# explorator_mainboard_v1_large_1_1_photo_.net
KiCad netlist of a schematic drawn in EAGLE
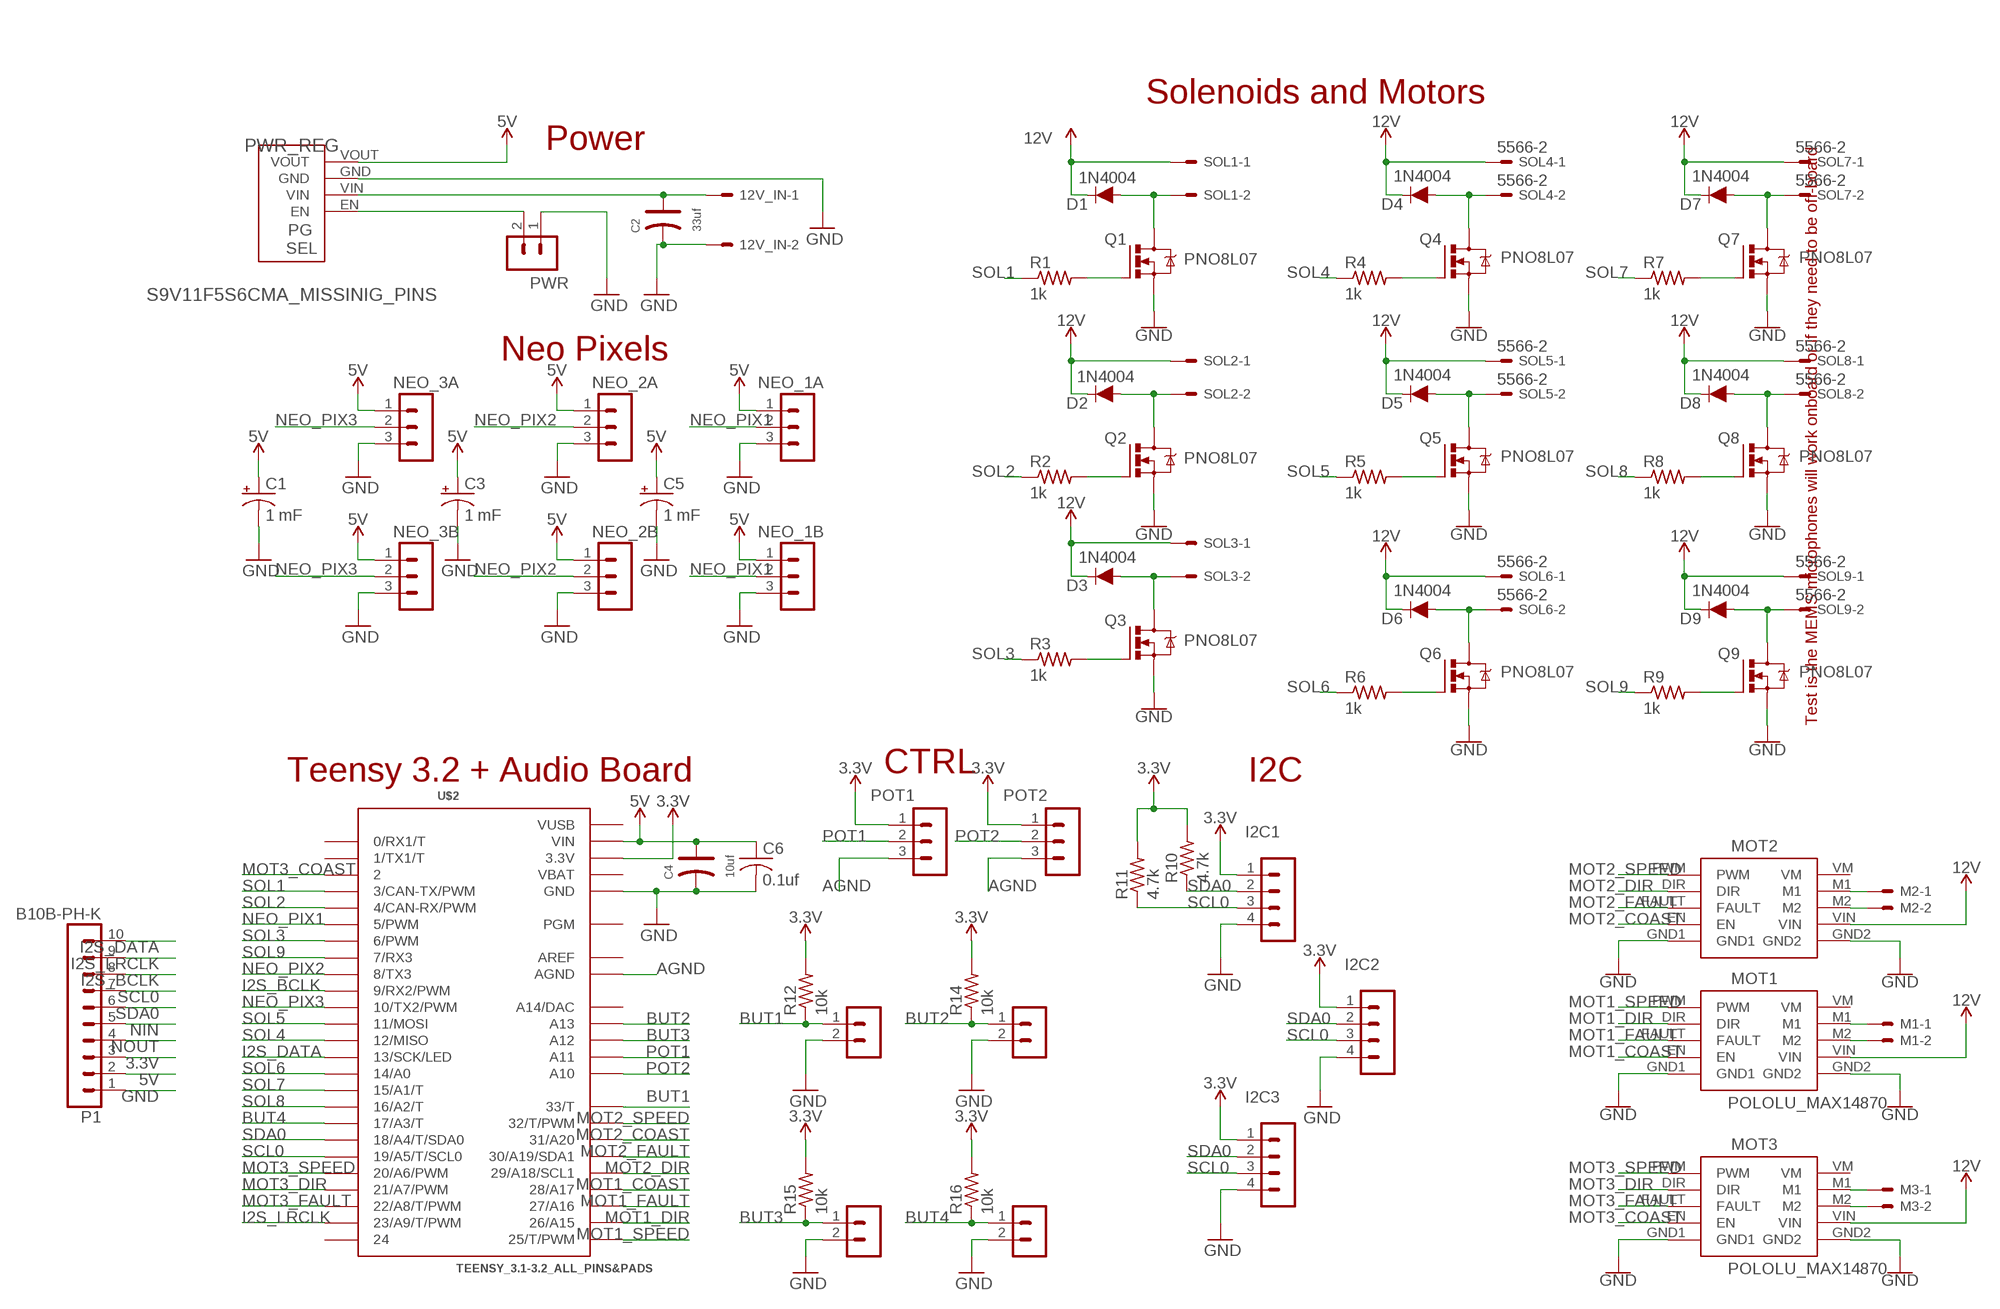
[diagram p0: schematic, sheet 1]

(export (version "E")
  (design (tool "Eeschema 10.0.6"))
  (components
    (comp (ref "12V_IN")
      (value "5566-2")
      (footprint "eagle-import:5566-2")
      (fields (field (name "MF") "MOLEX"))
      (libsource (lib "eagle-import") (part "5566-2"))
    )
    (comp (ref "BUT1")
      (value "B2B-PH-K")
      (footprint "eagle-import:B2B-PH-K")
      (libsource (lib "eagle-import") (part "B2B-PH-K"))
    )
    (comp (ref "BUT2")
      (value "B2B-PH-K")
      (footprint "eagle-import:B2B-PH-K")
      (libsource (lib "eagle-import") (part "B2B-PH-K"))
    )
    (comp (ref "BUT3")
      (value "B2B-PH-K")
      (footprint "eagle-import:B2B-PH-K")
      (libsource (lib "eagle-import") (part "B2B-PH-K"))
    )
    (comp (ref "BUT4")
      (value "B2B-PH-K")
      (footprint "eagle-import:B2B-PH-K")
      (libsource (lib "eagle-import") (part "B2B-PH-K"))
    )
    (comp (ref "C1")
      (value "1 mF")
      (footprint "eagle-import:UD-10X10_NICHICON")
      (libsource (lib "eagle-import") (part "CPOL-USUD-10X10"))
    )
    (comp (ref "C2")
      (value "33uf")
      (footprint "eagle-import:PC-D5.3MM")
      (fields (field (name "MPN") "KS 100uF/16V"))
      (libsource (lib "eagle-import") (part "DIP-ALUMINUM-47UF-16V(D5-H7MM)"))
    )
    (comp (ref "C3")
      (value "1 mF")
      (footprint "eagle-import:UD-10X10_NICHICON")
      (libsource (lib "eagle-import") (part "CPOL-USUD-10X10"))
    )
    (comp (ref "C4")
      (value "10uf")
      (footprint "eagle-import:PC-D5.3MM")
      (fields (field (name "MPN") "KS 100uF/16V"))
      (libsource (lib "eagle-import") (part "DIP-ALUMINUM-47UF-16V(D5-H7MM)"))
    )
    (comp (ref "C5")
      (value "1 mF")
      (footprint "eagle-import:UD-10X10_NICHICON")
      (libsource (lib "eagle-import") (part "CPOL-USUD-10X10"))
    )
    (comp (ref "C6")
      (value "0.1uf")
      (footprint "eagle-import:C2012")
      (libsource (lib "eagle-import") (part "C-USC2012"))
    )
    (comp (ref "D1")
      (value "1N4004")
      (footprint "eagle-import:DIOAD1138W86L465D235B")
      (libsource (lib "eagle-import") (part "1N4004"))
    )
    (comp (ref "D2")
      (value "1N4004")
      (footprint "eagle-import:DIOAD1138W86L465D235B")
      (libsource (lib "eagle-import") (part "1N4004"))
    )
    (comp (ref "D3")
      (value "1N4004")
      (footprint "eagle-import:DIOAD1138W86L465D235B")
      (libsource (lib "eagle-import") (part "1N4004"))
    )
    (comp (ref "D4")
      (value "1N4004")
      (footprint "eagle-import:DIOAD1138W86L465D235B")
      (libsource (lib "eagle-import") (part "1N4004"))
    )
    (comp (ref "D5")
      (value "1N4004")
      (footprint "eagle-import:DIOAD1138W86L465D235B")
      (libsource (lib "eagle-import") (part "1N4004"))
    )
    (comp (ref "D6")
      (value "1N4004")
      (footprint "eagle-import:DIOAD1138W86L465D235B")
      (libsource (lib "eagle-import") (part "1N4004"))
    )
    (comp (ref "D7")
      (value "1N4004")
      (footprint "eagle-import:DIOAD1138W86L465D235B")
      (libsource (lib "eagle-import") (part "1N4004"))
    )
    (comp (ref "D8")
      (value "1N4004")
      (footprint "eagle-import:DIOAD1138W86L465D235B")
      (libsource (lib "eagle-import") (part "1N4004"))
    )
    (comp (ref "D9")
      (value "1N4004")
      (footprint "eagle-import:DIOAD1138W86L465D235B")
      (libsource (lib "eagle-import") (part "1N4004"))
    )
    (comp (ref "I2C1")
      (value "B4B-PH-K")
      (footprint "eagle-import:B4B-PH-K")
      (libsource (lib "eagle-import") (part "B4B-PH-K"))
    )
    (comp (ref "I2C2")
      (value "B4B-PH-K")
      (footprint "eagle-import:B4B-PH-K")
      (libsource (lib "eagle-import") (part "B4B-PH-K"))
    )
    (comp (ref "I2C3")
      (value "B4B-PH-K")
      (footprint "eagle-import:B4B-PH-K")
      (libsource (lib "eagle-import") (part "B4B-PH-K"))
    )
    (comp (ref "M1")
      (value "5566-2")
      (footprint "eagle-import:5566-2")
      (fields (field (name "MF") "MOLEX"))
      (libsource (lib "eagle-import") (part "5566-2"))
    )
    (comp (ref "M2")
      (value "5566-2")
      (footprint "eagle-import:5566-2")
      (fields (field (name "MF") "MOLEX"))
      (libsource (lib "eagle-import") (part "5566-2"))
    )
    (comp (ref "M3")
      (value "5566-2")
      (footprint "eagle-import:5566-2")
      (fields (field (name "MF") "MOLEX"))
      (libsource (lib "eagle-import") (part "5566-2"))
    )
    (comp (ref "MOT1")
      (value "POLOLU_MAX14870")
      (footprint "eagle-import:POLOLU_MAX14870")
      (libsource (lib "eagle-import") (part "POLOLU_MAX14870"))
    )
    (comp (ref "MOT2")
      (value "POLOLU_MAX14870")
      (footprint "eagle-import:POLOLU_MAX14870")
      (libsource (lib "eagle-import") (part "POLOLU_MAX14870"))
    )
    (comp (ref "MOT3")
      (value "POLOLU_MAX14870")
      (footprint "eagle-import:POLOLU_MAX14870")
      (libsource (lib "eagle-import") (part "POLOLU_MAX14870"))
    )
    (comp (ref "NEO_1A")
      (value "B3B-PH-K")
      (footprint "eagle-import:B3B-PH-K")
      (libsource (lib "eagle-import") (part "B3B-PH-K"))
    )
    (comp (ref "NEO_1B")
      (value "B3B-PH-K")
      (footprint "eagle-import:B3B-PH-K")
      (libsource (lib "eagle-import") (part "B3B-PH-K"))
    )
    (comp (ref "NEO_2A")
      (value "B3B-PH-K")
      (footprint "eagle-import:B3B-PH-K")
      (libsource (lib "eagle-import") (part "B3B-PH-K"))
    )
    (comp (ref "NEO_2B")
      (value "B3B-PH-K")
      (footprint "eagle-import:B3B-PH-K")
      (libsource (lib "eagle-import") (part "B3B-PH-K"))
    )
    (comp (ref "NEO_3A")
      (value "B3B-PH-K")
      (footprint "eagle-import:B3B-PH-K")
      (libsource (lib "eagle-import") (part "B3B-PH-K"))
    )
    (comp (ref "NEO_3B")
      (value "B3B-PH-K")
      (footprint "eagle-import:B3B-PH-K")
      (libsource (lib "eagle-import") (part "B3B-PH-K"))
    )
    (comp (ref "P1")
      (value "B10B-PH-K")
      (footprint "eagle-import:B10B-PH-K")
      (libsource (lib "eagle-import") (part "B10B-PH-K"))
    )
    (comp (ref "POT1")
      (value "B3B-PH-K")
      (footprint "eagle-import:B3B-PH-K")
      (libsource (lib "eagle-import") (part "B3B-PH-K"))
    )
    (comp (ref "POT2")
      (value "B3B-PH-K")
      (footprint "eagle-import:B3B-PH-K")
      (libsource (lib "eagle-import") (part "B3B-PH-K"))
    )
    (comp (ref "PWR")
      (value "B2B-PH-K")
      (footprint "eagle-import:B2B-PH-K")
      (libsource (lib "eagle-import") (part "B2B-PH-K"))
    )
    (comp (ref "PWR_REG")
      (value "S9V11F5S6CMA_MISSINIG_PINS")
      (footprint "eagle-import:S9V11F3S5CMA_MISSING_PINS")
      (libsource (lib "eagle-import") (part "S9V11F5S6CMA_MISSINIG_PINS"))
    )
    (comp (ref "Q1")
      (value "PNO8L07")
      (footprint "eagle-import:TO220BV")
      (libsource (lib "eagle-import") (part "IRF540"))
    )
    (comp (ref "Q2")
      (value "PNO8L07")
      (footprint "eagle-import:TO220BV")
      (libsource (lib "eagle-import") (part "IRF540"))
    )
    (comp (ref "Q3")
      (value "PNO8L07")
      (footprint "eagle-import:TO220BV")
      (libsource (lib "eagle-import") (part "IRF540"))
    )
    (comp (ref "Q4")
      (value "PNO8L07")
      (footprint "eagle-import:TO220BV")
      (libsource (lib "eagle-import") (part "IRF540"))
    )
    (comp (ref "Q5")
      (value "PNO8L07")
      (footprint "eagle-import:TO220BV")
      (libsource (lib "eagle-import") (part "IRF540"))
    )
    (comp (ref "Q6")
      (value "PNO8L07")
      (footprint "eagle-import:TO220BV")
      (libsource (lib "eagle-import") (part "IRF540"))
    )
    (comp (ref "Q7")
      (value "PNO8L07")
      (footprint "eagle-import:TO220BV")
      (libsource (lib "eagle-import") (part "IRF540"))
    )
    (comp (ref "Q8")
      (value "PNO8L07")
      (footprint "eagle-import:TO220BV")
      (libsource (lib "eagle-import") (part "IRF540"))
    )
    (comp (ref "Q9")
      (value "PNO8L07")
      (footprint "eagle-import:TO220BV")
      (libsource (lib "eagle-import") (part "IRF540"))
    )
    (comp (ref "R1")
      (value "1k")
      (footprint "eagle-import:R0805")
      (libsource (lib "eagle-import") (part "R-US_R0805"))
    )
    (comp (ref "R2")
      (value "1k")
      (footprint "eagle-import:R0805")
      (libsource (lib "eagle-import") (part "R-US_R0805"))
    )
    (comp (ref "R3")
      (value "1k")
      (footprint "eagle-import:R0805")
      (libsource (lib "eagle-import") (part "R-US_R0805"))
    )
    (comp (ref "R4")
      (value "1k")
      (footprint "eagle-import:R0805")
      (libsource (lib "eagle-import") (part "R-US_R0805"))
    )
    (comp (ref "R5")
      (value "1k")
      (footprint "eagle-import:R0805")
      (libsource (lib "eagle-import") (part "R-US_R0805"))
    )
    (comp (ref "R6")
      (value "1k")
      (footprint "eagle-import:R0805")
      (libsource (lib "eagle-import") (part "R-US_R0805"))
    )
    (comp (ref "R7")
      (value "1k")
      (footprint "eagle-import:R0805")
      (libsource (lib "eagle-import") (part "R-US_R0805"))
    )
    (comp (ref "R8")
      (value "1k")
      (footprint "eagle-import:R0805")
      (libsource (lib "eagle-import") (part "R-US_R0805"))
    )
    (comp (ref "R9")
      (value "1k")
      (footprint "eagle-import:R0805")
      (libsource (lib "eagle-import") (part "R-US_R0805"))
    )
    (comp (ref "R10")
      (value "4.7k")
      (footprint "eagle-import:R0805")
      (libsource (lib "eagle-import") (part "R-US_R0805"))
    )
    (comp (ref "R11")
      (value "4.7k")
      (footprint "eagle-import:R0805")
      (libsource (lib "eagle-import") (part "R-US_R0805"))
    )
    (comp (ref "R12")
      (value "10k")
      (footprint "eagle-import:R0805")
      (libsource (lib "eagle-import") (part "R-US_R0805"))
    )
    (comp (ref "R14")
      (value "10k")
      (footprint "eagle-import:R0805")
      (libsource (lib "eagle-import") (part "R-US_R0805"))
    )
    (comp (ref "R15")
      (value "10k")
      (footprint "eagle-import:R0805")
      (libsource (lib "eagle-import") (part "R-US_R0805"))
    )
    (comp (ref "R16")
      (value "10k")
      (footprint "eagle-import:R0805")
      (libsource (lib "eagle-import") (part "R-US_R0805"))
    )
    (comp (ref "SOL1")
      (value "5566-2")
      (footprint "eagle-import:5566-2")
      (fields (field (name "MF") "MOLEX"))
      (libsource (lib "eagle-import") (part "5566-2"))
    )
    (comp (ref "SOL2")
      (value "5566-2")
      (footprint "eagle-import:5566-2")
      (fields (field (name "MF") "MOLEX"))
      (libsource (lib "eagle-import") (part "5566-2"))
    )
    (comp (ref "SOL3")
      (value "5566-2")
      (footprint "eagle-import:5566-2")
      (fields (field (name "MF") "MOLEX"))
      (libsource (lib "eagle-import") (part "5566-2"))
    )
    (comp (ref "SOL4")
      (value "5566-2")
      (footprint "eagle-import:5566-2")
      (fields (field (name "MF") "MOLEX"))
      (libsource (lib "eagle-import") (part "5566-2"))
    )
    (comp (ref "SOL5")
      (value "5566-2")
      (footprint "eagle-import:5566-2")
      (fields (field (name "MF") "MOLEX"))
      (libsource (lib "eagle-import") (part "5566-2"))
    )
    (comp (ref "SOL6")
      (value "5566-2")
      (footprint "eagle-import:5566-2")
      (fields (field (name "MF") "MOLEX"))
      (libsource (lib "eagle-import") (part "5566-2"))
    )
    (comp (ref "SOL7")
      (value "5566-2")
      (footprint "eagle-import:5566-2")
      (fields (field (name "MF") "MOLEX"))
      (libsource (lib "eagle-import") (part "5566-2"))
    )
    (comp (ref "SOL8")
      (value "5566-2")
      (footprint "eagle-import:5566-2")
      (fields (field (name "MF") "MOLEX"))
      (libsource (lib "eagle-import") (part "5566-2"))
    )
    (comp (ref "SOL9")
      (value "5566-2")
      (footprint "eagle-import:5566-2")
      (fields (field (name "MF") "MOLEX"))
      (libsource (lib "eagle-import") (part "5566-2"))
    )
    (comp (ref "U$2")
      (value "TEENSY_3.1-3.2_ALL_PINS&PADS")
      (footprint "eagle-import:TEENSY_3.0-3.2_ALL_PINS_&_PADS")
      (libsource (lib "eagle-import") (part "TEENSY_3.1-3.2_ALL_PINS&PADS"))
    )
  )
  (nets
    (net (code "1") (name "/AGND") (class "Default")
      (node (ref "POT1") (pin "3") (pinfunction "3_3") (pintype "passive"))
      (node (ref "POT2") (pin "3") (pinfunction "3_3") (pintype "passive"))
      (node (ref "U$2") (pin "AGND") (pinfunction "AGND_AGND") (pintype "power_in"))
    )
    (net (code "2") (name "/AREF") (class "Default")
      (node (ref "U$2") (pin "AREF") (pinfunction "AREF_AREF") (pintype "power_in"))
    )
    (net (code "3") (name "/BUT1") (class "Default")
      (node (ref "BUT1") (pin "1") (pinfunction "1_1") (pintype "passive"))
      (node (ref "R12") (pin "1") (pinfunction "1_1") (pintype "passive"))
      (node (ref "U$2") (pin "33") (pinfunction "33/T_33") (pintype "bidirectional"))
    )
    (net (code "4") (name "/BUT2") (class "Default")
      (node (ref "BUT2") (pin "1") (pinfunction "1_1") (pintype "passive"))
      (node (ref "R14") (pin "1") (pinfunction "1_1") (pintype "passive"))
      (node (ref "U$2") (pin "A13") (pinfunction "A13_A13") (pintype "bidirectional"))
    )
    (net (code "5") (name "/BUT3") (class "Default")
      (node (ref "BUT3") (pin "1") (pinfunction "1_1") (pintype "passive"))
      (node (ref "R15") (pin "1") (pinfunction "1_1") (pintype "passive"))
      (node (ref "U$2") (pin "A12") (pinfunction "A12_A12") (pintype "bidirectional"))
    )
    (net (code "6") (name "/BUT4") (class "Default")
      (node (ref "BUT4") (pin "1") (pinfunction "1_1") (pintype "passive"))
      (node (ref "R16") (pin "1") (pinfunction "1_1") (pintype "passive"))
      (node (ref "U$2") (pin "17/A3") (pinfunction "17/A3/T_17/A3") (pintype "bidirectional"))
    )
    (net (code "7") (name "/I2S_BCLK") (class "Default")
      (node (ref "P1") (pin "8") (pinfunction "8_8") (pintype "passive"))
      (node (ref "U$2") (pin "9") (pinfunction "9/RX2/PWM_9") (pintype "bidirectional"))
    )
    (net (code "8") (name "/I2S_DATA") (class "Default")
      (node (ref "P1") (pin "10") (pinfunction "10_10") (pintype "passive"))
      (node (ref "U$2") (pin "13") (pinfunction "13/SCK/LED_13") (pintype "bidirectional"))
    )
    (net (code "9") (name "/I2S_LRCLK") (class "Default")
      (node (ref "P1") (pin "9") (pinfunction "9_9") (pintype "passive"))
      (node (ref "U$2") (pin "23/A9") (pinfunction "23/A9/T/PWM_23/A9") (pintype "bidirectional"))
    )
    (net (code "10") (name "/MOT1_COAST") (class "Default")
      (node (ref "MOT1") (pin "EN") (pinfunction "EN_EN") (pintype "bidirectional"))
      (node (ref "U$2") (pin "28") (pinfunction "28/A17_28") (pintype "bidirectional"))
    )
    (net (code "11") (name "/MOT1_DIR") (class "Default")
      (node (ref "MOT1") (pin "DIR") (pinfunction "DIR_DIR") (pintype "bidirectional"))
      (node (ref "U$2") (pin "26") (pinfunction "26/A15_26") (pintype "bidirectional"))
    )
    (net (code "12") (name "/MOT1_FAULT") (class "Default")
      (node (ref "MOT1") (pin "FAULT") (pinfunction "FAULT_FAULT") (pintype "bidirectional"))
      (node (ref "U$2") (pin "27") (pinfunction "27/A16_27") (pintype "bidirectional"))
    )
    (net (code "13") (name "/MOT1_SPEED") (class "Default")
      (node (ref "MOT1") (pin "PWM") (pinfunction "PWM_PWM") (pintype "bidirectional"))
      (node (ref "U$2") (pin "25") (pinfunction "25/T/PWM_25") (pintype "bidirectional"))
    )
    (net (code "14") (name "/MOT2_COAST") (class "Default")
      (node (ref "MOT2") (pin "EN") (pinfunction "EN_EN") (pintype "bidirectional"))
      (node (ref "U$2") (pin "31") (pinfunction "31/A20_31") (pintype "bidirectional"))
    )
    (net (code "15") (name "/MOT2_DIR") (class "Default")
      (node (ref "MOT2") (pin "DIR") (pinfunction "DIR_DIR") (pintype "bidirectional"))
      (node (ref "U$2") (pin "29") (pinfunction "29/A18/SCL1_29") (pintype "bidirectional"))
    )
    (net (code "16") (name "/MOT2_FAULT") (class "Default")
      (node (ref "MOT2") (pin "FAULT") (pinfunction "FAULT_FAULT") (pintype "bidirectional"))
      (node (ref "U$2") (pin "30") (pinfunction "30/A19/SDA1_30") (pintype "bidirectional"))
    )
    (net (code "17") (name "/MOT2_SPEED") (class "Default")
      (node (ref "MOT2") (pin "PWM") (pinfunction "PWM_PWM") (pintype "bidirectional"))
      (node (ref "U$2") (pin "32") (pinfunction "32/T/PWM_32") (pintype "bidirectional"))
    )
    (net (code "18") (name "/MOT3_COAST") (class "Default")
      (node (ref "MOT3") (pin "EN") (pinfunction "EN_EN") (pintype "bidirectional"))
      (node (ref "U$2") (pin "2") (pinfunction "2_2") (pintype "bidirectional"))
    )
    (net (code "19") (name "/MOT3_DIR") (class "Default")
      (node (ref "MOT3") (pin "DIR") (pinfunction "DIR_DIR") (pintype "bidirectional"))
      (node (ref "U$2") (pin "21/A7") (pinfunction "21/A7/PWM_21/A7") (pintype "bidirectional"))
    )
    (net (code "20") (name "/MOT3_FAULT") (class "Default")
      (node (ref "MOT3") (pin "FAULT") (pinfunction "FAULT_FAULT") (pintype "bidirectional"))
      (node (ref "U$2") (pin "22/A8") (pinfunction "22/A8/T/PWM_22/A8") (pintype "bidirectional"))
    )
    (net (code "21") (name "/MOT3_SPEED") (class "Default")
      (node (ref "MOT3") (pin "PWM") (pinfunction "PWM_PWM") (pintype "bidirectional"))
      (node (ref "U$2") (pin "20/A6") (pinfunction "20/A6/PWM_20/A6") (pintype "bidirectional"))
    )
    (net (code "22") (name "/NEO_PIX1") (class "Default")
      (node (ref "NEO_1A") (pin "2") (pinfunction "2_2") (pintype "passive"))
      (node (ref "NEO_1B") (pin "2") (pinfunction "2_2") (pintype "passive"))
      (node (ref "U$2") (pin "5") (pinfunction "5/PWM_5") (pintype "bidirectional"))
    )
    (net (code "23") (name "/NEO_PIX2") (class "Default")
      (node (ref "NEO_2A") (pin "2") (pinfunction "2_2") (pintype "passive"))
      (node (ref "NEO_2B") (pin "2") (pinfunction "2_2") (pintype "passive"))
      (node (ref "U$2") (pin "8") (pinfunction "8/TX3_8") (pintype "bidirectional"))
    )
    (net (code "24") (name "/NEO_PIX3") (class "Default")
      (node (ref "NEO_3A") (pin "2") (pinfunction "2_2") (pintype "passive"))
      (node (ref "NEO_3B") (pin "2") (pinfunction "2_2") (pintype "passive"))
      (node (ref "U$2") (pin "10") (pinfunction "10/TX2/PWM_10") (pintype "bidirectional"))
    )
    (net (code "25") (name "/NIN") (class "Default")
      (node (ref "P1") (pin "5") (pinfunction "5_5") (pintype "passive"))
    )
    (net (code "26") (name "/NOUT") (class "Default")
      (node (ref "P1") (pin "4") (pinfunction "4_4") (pintype "passive"))
    )
    (net (code "27") (name "/POT1") (class "Default")
      (node (ref "POT1") (pin "2") (pinfunction "2_2") (pintype "passive"))
      (node (ref "U$2") (pin "A11") (pinfunction "A11_A11") (pintype "bidirectional"))
    )
    (net (code "28") (name "/POT2") (class "Default")
      (node (ref "POT2") (pin "2") (pinfunction "2_2") (pintype "passive"))
      (node (ref "U$2") (pin "A10") (pinfunction "A10_A10") (pintype "bidirectional"))
    )
    (net (code "29") (name "/SCL0") (class "Default")
      (node (ref "I2C1") (pin "3") (pinfunction "3_3") (pintype "passive"))
      (node (ref "I2C2") (pin "3") (pinfunction "3_3") (pintype "passive"))
      (node (ref "I2C3") (pin "3") (pinfunction "3_3") (pintype "passive"))
      (node (ref "P1") (pin "7") (pinfunction "7_7") (pintype "passive"))
      (node (ref "R11") (pin "1") (pinfunction "1_1") (pintype "passive"))
      (node (ref "U$2") (pin "19/A5") (pinfunction "19/A5/T/SCL0_19/A5") (pintype "bidirectional"))
    )
    (net (code "30") (name "/SDA0") (class "Default")
      (node (ref "I2C1") (pin "2") (pinfunction "2_2") (pintype "passive"))
      (node (ref "I2C2") (pin "2") (pinfunction "2_2") (pintype "passive"))
      (node (ref "I2C3") (pin "2") (pinfunction "2_2") (pintype "passive"))
      (node (ref "P1") (pin "6") (pinfunction "6_6") (pintype "passive"))
      (node (ref "R10") (pin "1") (pinfunction "1_1") (pintype "passive"))
      (node (ref "U$2") (pin "18/A4") (pinfunction "18/A4/T/SDA0_18/A4") (pintype "bidirectional"))
    )
    (net (code "31") (name "/SOL1") (class "Default")
      (node (ref "R1") (pin "1") (pinfunction "1_1") (pintype "passive"))
      (node (ref "U$2") (pin "3") (pinfunction "3/CAN-TX/PWM_3") (pintype "bidirectional"))
    )
    (net (code "32") (name "/SOL2") (class "Default")
      (node (ref "R2") (pin "1") (pinfunction "1_1") (pintype "passive"))
      (node (ref "U$2") (pin "4") (pinfunction "4/CAN-RX/PWM_4") (pintype "bidirectional"))
    )
    (net (code "33") (name "/SOL3") (class "Default")
      (node (ref "R3") (pin "1") (pinfunction "1_1") (pintype "passive"))
      (node (ref "U$2") (pin "6") (pinfunction "6/PWM_6") (pintype "bidirectional"))
    )
    (net (code "34") (name "/SOL4") (class "Default")
      (node (ref "R4") (pin "1") (pinfunction "1_1") (pintype "passive"))
      (node (ref "U$2") (pin "12") (pinfunction "12/MISO_12") (pintype "bidirectional"))
    )
    (net (code "35") (name "/SOL5") (class "Default")
      (node (ref "R5") (pin "1") (pinfunction "1_1") (pintype "passive"))
      (node (ref "U$2") (pin "11") (pinfunction "11/MOSI_11") (pintype "bidirectional"))
    )
    (net (code "36") (name "/SOL6") (class "Default")
      (node (ref "R6") (pin "1") (pinfunction "1_1") (pintype "passive"))
      (node (ref "U$2") (pin "14/A0") (pinfunction "14/A0_14/A0") (pintype "bidirectional"))
    )
    (net (code "37") (name "/SOL7") (class "Default")
      (node (ref "R7") (pin "1") (pinfunction "1_1") (pintype "passive"))
      (node (ref "U$2") (pin "15/A1") (pinfunction "15/A1/T_15/A1") (pintype "bidirectional"))
    )
    (net (code "38") (name "/SOL8") (class "Default")
      (node (ref "R8") (pin "1") (pinfunction "1_1") (pintype "passive"))
      (node (ref "U$2") (pin "16/A2") (pinfunction "16/A2/T_16/A2") (pintype "bidirectional"))
    )
    (net (code "39") (name "/SOL9") (class "Default")
      (node (ref "R9") (pin "1") (pinfunction "1_1") (pintype "passive"))
      (node (ref "U$2") (pin "7") (pinfunction "7/RX3_7") (pintype "bidirectional"))
    )
    (net (code "40") (name "/VBAT") (class "Default")
      (node (ref "U$2") (pin "VBAT") (pinfunction "VBAT_VBAT") (pintype "power_in"))
    )
    (net (code "41") (name "/VUSB") (class "Default")
      (node (ref "U$2") (pin "VUSB") (pinfunction "VUSB_VUSB") (pintype "power_in"))
    )
    (net (code "42") (name "3.3V") (class "Default")
      (node (ref "I2C1") (pin "1") (pinfunction "1_1") (pintype "passive"))
      (node (ref "I2C2") (pin "1") (pinfunction "1_1") (pintype "passive"))
      (node (ref "I2C3") (pin "1") (pinfunction "1_1") (pintype "passive"))
      (node (ref "P1") (pin "3") (pinfunction "3_3") (pintype "passive"))
      (node (ref "POT1") (pin "1") (pinfunction "1_1") (pintype "passive"))
      (node (ref "POT2") (pin "1") (pinfunction "1_1") (pintype "passive"))
      (node (ref "R10") (pin "2") (pinfunction "2_2") (pintype "passive"))
      (node (ref "R11") (pin "2") (pinfunction "2_2") (pintype "passive"))
      (node (ref "R12") (pin "2") (pinfunction "2_2") (pintype "passive"))
      (node (ref "R14") (pin "2") (pinfunction "2_2") (pintype "passive"))
      (node (ref "R15") (pin "2") (pinfunction "2_2") (pintype "passive"))
      (node (ref "R16") (pin "2") (pinfunction "2_2") (pintype "passive"))
      (node (ref "U$2") (pin "3.3V") (pinfunction "3.3V_3.3V") (pintype "power_in"))
      (node (ref "U$2") (pin "3.3V1") (pinfunction "3.3V_3.3V1") (pintype "power_in"))
      (node (ref "U$2") (pin "3.3V2") (pinfunction "3.3V_3.3V2") (pintype "power_in"))
    )
    (net (code "43") (name "5V") (class "Default")
      (node (ref "C1") (pin "+") (pinfunction "+_+") (pintype "passive"))
      (node (ref "C3") (pin "+") (pinfunction "+_+") (pintype "passive"))
      (node (ref "C4") (pin "+") (pinfunction "+_+") (pintype "passive"))
      (node (ref "C5") (pin "+") (pinfunction "+_+") (pintype "passive"))
      (node (ref "C6") (pin "1") (pinfunction "1_1") (pintype "passive"))
      (node (ref "NEO_1A") (pin "1") (pinfunction "1_1") (pintype "passive"))
      (node (ref "NEO_1B") (pin "1") (pinfunction "1_1") (pintype "passive"))
      (node (ref "NEO_2A") (pin "1") (pinfunction "1_1") (pintype "passive"))
      (node (ref "NEO_2B") (pin "1") (pinfunction "1_1") (pintype "passive"))
      (node (ref "NEO_3A") (pin "1") (pinfunction "1_1") (pintype "passive"))
      (node (ref "NEO_3B") (pin "1") (pinfunction "1_1") (pintype "passive"))
      (node (ref "P1") (pin "2") (pinfunction "2_2") (pintype "passive"))
      (node (ref "PWR_REG") (pin "VOUT") (pinfunction "VOUT_VOUT") (pintype "bidirectional"))
      (node (ref "U$2") (pin "VIN") (pinfunction "VIN_VIN") (pintype "power_in"))
    )
    (net (code "44") (name "12V") (class "Default")
      (node (ref "12V_IN") (pin "1") (pinfunction "S_1") (pintype "passive"))
      (node (ref "C2") (pin "+") (pinfunction "+_+") (pintype "passive"))
      (node (ref "D1") (pin "2") (pinfunction "C_2") (pintype "passive"))
      (node (ref "D2") (pin "2") (pinfunction "C_2") (pintype "passive"))
      (node (ref "D3") (pin "2") (pinfunction "C_2") (pintype "passive"))
      (node (ref "D4") (pin "2") (pinfunction "C_2") (pintype "passive"))
      (node (ref "D5") (pin "2") (pinfunction "C_2") (pintype "passive"))
      (node (ref "D6") (pin "2") (pinfunction "C_2") (pintype "passive"))
      (node (ref "D7") (pin "2") (pinfunction "C_2") (pintype "passive"))
      (node (ref "D8") (pin "2") (pinfunction "C_2") (pintype "passive"))
      (node (ref "D9") (pin "2") (pinfunction "C_2") (pintype "passive"))
      (node (ref "MOT1") (pin "VIN") (pinfunction "VIN_VIN") (pintype "bidirectional"))
      (node (ref "MOT2") (pin "VIN") (pinfunction "VIN_VIN") (pintype "bidirectional"))
      (node (ref "MOT3") (pin "VIN") (pinfunction "VIN_VIN") (pintype "bidirectional"))
      (node (ref "PWR_REG") (pin "VIN") (pinfunction "VIN_VIN") (pintype "bidirectional"))
      (node (ref "SOL1") (pin "1") (pinfunction "S_1") (pintype "passive"))
      (node (ref "SOL2") (pin "1") (pinfunction "S_1") (pintype "passive"))
      (node (ref "SOL3") (pin "1") (pinfunction "S_1") (pintype "passive"))
      (node (ref "SOL4") (pin "1") (pinfunction "S_1") (pintype "passive"))
      (node (ref "SOL5") (pin "1") (pinfunction "S_1") (pintype "passive"))
      (node (ref "SOL6") (pin "1") (pinfunction "S_1") (pintype "passive"))
      (node (ref "SOL7") (pin "1") (pinfunction "S_1") (pintype "passive"))
      (node (ref "SOL8") (pin "1") (pinfunction "S_1") (pintype "passive"))
      (node (ref "SOL9") (pin "1") (pinfunction "S_1") (pintype "passive"))
    )
    (net (code "45") (name "GND") (class "Default")
      (node (ref "12V_IN") (pin "2") (pinfunction "S_2") (pintype "passive"))
      (node (ref "BUT1") (pin "2") (pinfunction "2_2") (pintype "passive"))
      (node (ref "BUT2") (pin "2") (pinfunction "2_2") (pintype "passive"))
      (node (ref "BUT3") (pin "2") (pinfunction "2_2") (pintype "passive"))
      (node (ref "BUT4") (pin "2") (pinfunction "2_2") (pintype "passive"))
      (node (ref "C1") (pin "-") (pinfunction "-_-") (pintype "passive"))
      (node (ref "C2") (pin "-") (pinfunction "-_-") (pintype "passive"))
      (node (ref "C3") (pin "-") (pinfunction "-_-") (pintype "passive"))
      (node (ref "C4") (pin "-") (pinfunction "-_-") (pintype "passive"))
      (node (ref "C5") (pin "-") (pinfunction "-_-") (pintype "passive"))
      (node (ref "C6") (pin "2") (pinfunction "2_2") (pintype "passive"))
      (node (ref "I2C1") (pin "4") (pinfunction "4_4") (pintype "passive"))
      (node (ref "I2C2") (pin "4") (pinfunction "4_4") (pintype "passive"))
      (node (ref "I2C3") (pin "4") (pinfunction "4_4") (pintype "passive"))
      (node (ref "MOT1") (pin "GND1") (pinfunction "GND1_GND1") (pintype "bidirectional"))
      (node (ref "MOT1") (pin "GND2") (pinfunction "GND2_GND2") (pintype "bidirectional"))
      (node (ref "MOT2") (pin "GND1") (pinfunction "GND1_GND1") (pintype "bidirectional"))
      (node (ref "MOT2") (pin "GND2") (pinfunction "GND2_GND2") (pintype "bidirectional"))
      (node (ref "MOT3") (pin "GND1") (pinfunction "GND1_GND1") (pintype "bidirectional"))
      (node (ref "MOT3") (pin "GND2") (pinfunction "GND2_GND2") (pintype "bidirectional"))
      (node (ref "NEO_1A") (pin "3") (pinfunction "3_3") (pintype "passive"))
      (node (ref "NEO_1B") (pin "3") (pinfunction "3_3") (pintype "passive"))
      (node (ref "NEO_2A") (pin "3") (pinfunction "3_3") (pintype "passive"))
      (node (ref "NEO_2B") (pin "3") (pinfunction "3_3") (pintype "passive"))
      (node (ref "NEO_3A") (pin "3") (pinfunction "3_3") (pintype "passive"))
      (node (ref "NEO_3B") (pin "3") (pinfunction "3_3") (pintype "passive"))
      (node (ref "P1") (pin "1") (pinfunction "1_1") (pintype "passive"))
      (node (ref "PWR") (pin "1") (pinfunction "1_1") (pintype "passive"))
      (node (ref "PWR_REG") (pin "GND") (pinfunction "GND_GND") (pintype "bidirectional"))
      (node (ref "Q1") (pin "S") (pinfunction "S_S") (pintype "passive"))
      (node (ref "Q2") (pin "S") (pinfunction "S_S") (pintype "passive"))
      (node (ref "Q3") (pin "S") (pinfunction "S_S") (pintype "passive"))
      (node (ref "Q4") (pin "S") (pinfunction "S_S") (pintype "passive"))
      (node (ref "Q5") (pin "S") (pinfunction "S_S") (pintype "passive"))
      (node (ref "Q6") (pin "S") (pinfunction "S_S") (pintype "passive"))
      (node (ref "Q7") (pin "S") (pinfunction "S_S") (pintype "passive"))
      (node (ref "Q8") (pin "S") (pinfunction "S_S") (pintype "passive"))
      (node (ref "Q9") (pin "S") (pinfunction "S_S") (pintype "passive"))
      (node (ref "U$2") (pin "GND") (pinfunction "GND_GND") (pintype "power_in"))
      (node (ref "U$2") (pin "GND1") (pinfunction "GND_GND1") (pintype "power_in"))
      (node (ref "U$2") (pin "GND2") (pinfunction "GND_GND2") (pintype "power_in"))
    )
    (net (code "46") (name "Net-(D1-A)") (class "Default")
      (node (ref "D1") (pin "1") (pinfunction "A_1") (pintype "passive"))
      (node (ref "Q1") (pin "D") (pinfunction "D_D") (pintype "passive"))
      (node (ref "SOL1") (pin "2") (pinfunction "S_2") (pintype "passive"))
    )
    (net (code "47") (name "Net-(D2-A)") (class "Default")
      (node (ref "D2") (pin "1") (pinfunction "A_1") (pintype "passive"))
      (node (ref "Q2") (pin "D") (pinfunction "D_D") (pintype "passive"))
      (node (ref "SOL2") (pin "2") (pinfunction "S_2") (pintype "passive"))
    )
    (net (code "48") (name "Net-(D3-A)") (class "Default")
      (node (ref "D3") (pin "1") (pinfunction "A_1") (pintype "passive"))
      (node (ref "Q3") (pin "D") (pinfunction "D_D") (pintype "passive"))
      (node (ref "SOL3") (pin "2") (pinfunction "S_2") (pintype "passive"))
    )
    (net (code "49") (name "Net-(D4-A)") (class "Default")
      (node (ref "D4") (pin "1") (pinfunction "A_1") (pintype "passive"))
      (node (ref "Q4") (pin "D") (pinfunction "D_D") (pintype "passive"))
      (node (ref "SOL4") (pin "2") (pinfunction "S_2") (pintype "passive"))
    )
    (net (code "50") (name "Net-(D5-A)") (class "Default")
      (node (ref "D5") (pin "1") (pinfunction "A_1") (pintype "passive"))
      (node (ref "Q5") (pin "D") (pinfunction "D_D") (pintype "passive"))
      (node (ref "SOL5") (pin "2") (pinfunction "S_2") (pintype "passive"))
    )
    (net (code "51") (name "Net-(D6-A)") (class "Default")
      (node (ref "D6") (pin "1") (pinfunction "A_1") (pintype "passive"))
      (node (ref "Q6") (pin "D") (pinfunction "D_D") (pintype "passive"))
      (node (ref "SOL6") (pin "2") (pinfunction "S_2") (pintype "passive"))
    )
    (net (code "52") (name "Net-(D7-A)") (class "Default")
      (node (ref "D7") (pin "1") (pinfunction "A_1") (pintype "passive"))
      (node (ref "Q7") (pin "D") (pinfunction "D_D") (pintype "passive"))
      (node (ref "SOL7") (pin "2") (pinfunction "S_2") (pintype "passive"))
    )
    (net (code "53") (name "Net-(D8-A)") (class "Default")
      (node (ref "D8") (pin "1") (pinfunction "A_1") (pintype "passive"))
      (node (ref "Q8") (pin "D") (pinfunction "D_D") (pintype "passive"))
      (node (ref "SOL8") (pin "2") (pinfunction "S_2") (pintype "passive"))
    )
    (net (code "54") (name "Net-(D9-A)") (class "Default")
      (node (ref "D9") (pin "1") (pinfunction "A_1") (pintype "passive"))
      (node (ref "Q9") (pin "D") (pinfunction "D_D") (pintype "passive"))
      (node (ref "SOL9") (pin "2") (pinfunction "S_2") (pintype "passive"))
    )
    (net (code "55") (name "Net-(M1A-S)") (class "Default")
      (node (ref "M1") (pin "1") (pinfunction "S_1") (pintype "passive"))
      (node (ref "MOT1") (pin "M1") (pinfunction "M1_M1") (pintype "bidirectional"))
    )
    (net (code "56") (name "Net-(M1B-S)") (class "Default")
      (node (ref "M1") (pin "2") (pinfunction "S_2") (pintype "passive"))
      (node (ref "MOT1") (pin "M2") (pinfunction "M2_M2") (pintype "bidirectional"))
    )
    (net (code "57") (name "Net-(M2A-S)") (class "Default")
      (node (ref "M2") (pin "1") (pinfunction "S_1") (pintype "passive"))
      (node (ref "MOT2") (pin "M1") (pinfunction "M1_M1") (pintype "bidirectional"))
    )
    (net (code "58") (name "Net-(M2B-S)") (class "Default")
      (node (ref "M2") (pin "2") (pinfunction "S_2") (pintype "passive"))
      (node (ref "MOT2") (pin "M2") (pinfunction "M2_M2") (pintype "bidirectional"))
    )
    (net (code "59") (name "Net-(M3A-S)") (class "Default")
      (node (ref "M3") (pin "1") (pinfunction "S_1") (pintype "passive"))
      (node (ref "MOT3") (pin "M1") (pinfunction "M1_M1") (pintype "bidirectional"))
    )
    (net (code "60") (name "Net-(M3B-S)") (class "Default")
      (node (ref "M3") (pin "2") (pinfunction "S_2") (pintype "passive"))
      (node (ref "MOT3") (pin "M2") (pinfunction "M2_M2") (pintype "bidirectional"))
    )
    (net (code "61") (name "Net-(PWR-Pad2)") (class "Default")
      (node (ref "PWR") (pin "2") (pinfunction "2_2") (pintype "passive"))
      (node (ref "PWR_REG") (pin "EN") (pinfunction "EN_EN") (pintype "bidirectional"))
    )
    (net (code "62") (name "Net-(Q1-PadG)") (class "Default")
      (node (ref "Q1") (pin "G") (pinfunction "G_G") (pintype "passive"))
      (node (ref "R1") (pin "2") (pinfunction "2_2") (pintype "passive"))
    )
    (net (code "63") (name "Net-(Q2-PadG)") (class "Default")
      (node (ref "Q2") (pin "G") (pinfunction "G_G") (pintype "passive"))
      (node (ref "R2") (pin "2") (pinfunction "2_2") (pintype "passive"))
    )
    (net (code "64") (name "Net-(Q3-PadG)") (class "Default")
      (node (ref "Q3") (pin "G") (pinfunction "G_G") (pintype "passive"))
      (node (ref "R3") (pin "2") (pinfunction "2_2") (pintype "passive"))
    )
    (net (code "65") (name "Net-(Q4-PadG)") (class "Default")
      (node (ref "Q4") (pin "G") (pinfunction "G_G") (pintype "passive"))
      (node (ref "R4") (pin "2") (pinfunction "2_2") (pintype "passive"))
    )
    (net (code "66") (name "Net-(Q5-PadG)") (class "Default")
      (node (ref "Q5") (pin "G") (pinfunction "G_G") (pintype "passive"))
      (node (ref "R5") (pin "2") (pinfunction "2_2") (pintype "passive"))
    )
    (net (code "67") (name "Net-(Q6-PadG)") (class "Default")
      (node (ref "Q6") (pin "G") (pinfunction "G_G") (pintype "passive"))
      (node (ref "R6") (pin "2") (pinfunction "2_2") (pintype "passive"))
    )
    (net (code "68") (name "Net-(Q7-PadG)") (class "Default")
      (node (ref "Q7") (pin "G") (pinfunction "G_G") (pintype "passive"))
      (node (ref "R7") (pin "2") (pinfunction "2_2") (pintype "passive"))
    )
    (net (code "69") (name "Net-(Q8-PadG)") (class "Default")
      (node (ref "Q8") (pin "G") (pinfunction "G_G") (pintype "passive"))
      (node (ref "R8") (pin "2") (pinfunction "2_2") (pintype "passive"))
    )
    (net (code "70") (name "Net-(Q9-PadG)") (class "Default")
      (node (ref "Q9") (pin "G") (pinfunction "G_G") (pintype "passive"))
      (node (ref "R9") (pin "2") (pinfunction "2_2") (pintype "passive"))
    )
    (net (code "71") (name "unconnected-(MOT1-PadVM)") (class "Default")
      (node (ref "MOT1") (pin "VM") (pinfunction "VM_VM") (pintype "bidirectional"))
    )
    (net (code "72") (name "unconnected-(MOT2-PadVM)") (class "Default")
      (node (ref "MOT2") (pin "VM") (pinfunction "VM_VM") (pintype "bidirectional"))
    )
    (net (code "73") (name "unconnected-(MOT3-PadVM)") (class "Default")
      (node (ref "MOT3") (pin "VM") (pinfunction "VM_VM") (pintype "bidirectional"))
    )
    (net (code "74") (name "unconnected-(U$2-0{slash}RX1{slash}T-Pad0)") (class "Default")
      (node (ref "U$2") (pin "0") (pinfunction "0/RX1/T_0") (pintype "bidirectional"))
    )
    (net (code "75") (name "unconnected-(U$2-1{slash}TX1{slash}T-Pad1)") (class "Default")
      (node (ref "U$2") (pin "1") (pinfunction "1/TX1/T_1") (pintype "bidirectional"))
    )
    (net (code "76") (name "unconnected-(U$2-A14{slash}DAC-PadRESET{slash}DAC)") (class "Default")
      (node (ref "U$2") (pin "RESET/DAC") (pinfunction "A14/DAC_RESET/DAC") (pintype "bidirectional"))
    )
    (net (code "77") (name "unconnected-(U$2-Pad24)") (class "Default")
      (node (ref "U$2") (pin "24") (pinfunction "24_24") (pintype "bidirectional"))
    )
    (net (code "78") (name "unconnected-(U$2-PadPGM)") (class "Default")
      (node (ref "U$2") (pin "PGM") (pinfunction "PGM_PGM") (pintype "bidirectional"))
    )
  )
)
